# Jetson_Nano_without_CAN.net
KiCad netlist of a schematic drawn in EAGLE
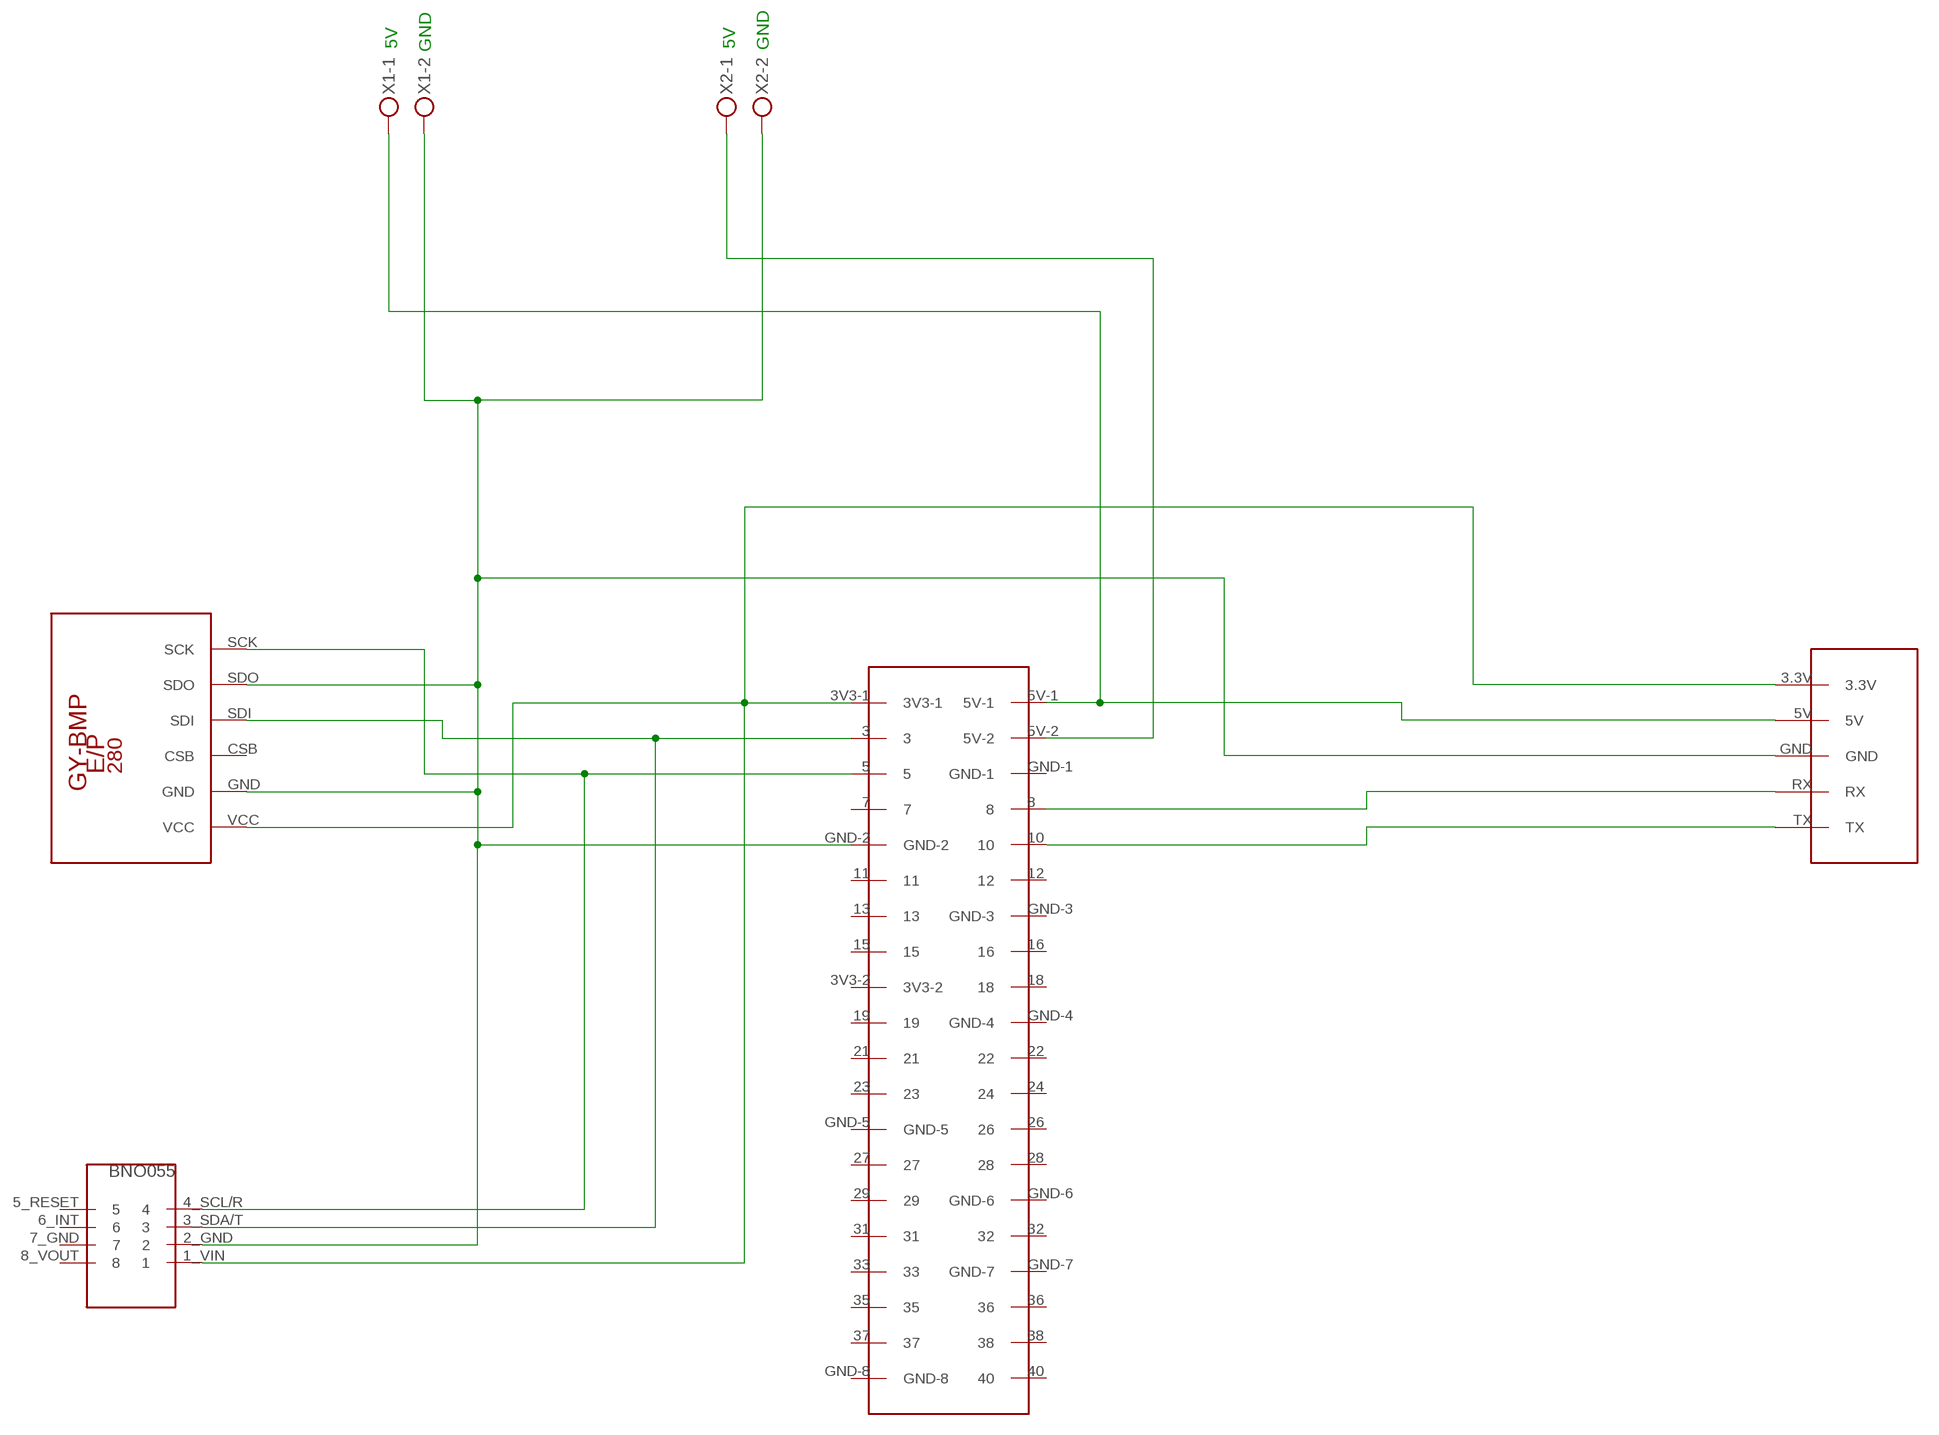
[diagram p0: schematic, sheet 1]

(export (version "E")
  (design (tool "Eeschema 10.0.6"))
  (components
    (comp (ref "JN1")
      (value "JETSON_NANO")
      (footprint "eagle-import:JETSON_NANO")
      (libsource (lib "eagle-import") (part "JETSON_NANO"))
    )
    (comp (ref "U$1")
      (value "GY-BPM280")
      (footprint "eagle-import:GY-BMP280-FOOTPRINT")
      (libsource (lib "eagle-import") (part "GY-BPM280"))
    )
    (comp (ref "U$2")
      (value "BNO055")
      (footprint "eagle-import:BNO055")
      (libsource (lib "eagle-import") (part "BNO055"))
    )
    (comp (ref "U$3")
      (value "WIRELESS_PINS")
      (footprint "eagle-import:WIRELESS_PINS")
      (libsource (lib "eagle-import") (part "WIRELESS_PINS"))
    )
    (comp (ref "X1")
      (value "MKDSN1,5/4-5,08")
      (footprint "eagle-import:MKDSN1,5_4-5,08")
      (libsource (lib "eagle-import") (part "MKDSN1,5/4-5,08"))
    )
    (comp (ref "X2")
      (value "MKDSN1,5/4-5,08")
      (footprint "eagle-import:MKDSN1,5_4-5,08")
      (libsource (lib "eagle-import") (part "MKDSN1,5/4-5,08"))
    )
  )
  (nets
    (net (code "1") (name "Net-(JN1-Pad8)") (class "Default")
      (node (ref "JN1") (pin "8") (pinfunction "8_8") (pintype "bidirectional"))
      (node (ref "U$3") (pin "RX") (pinfunction "RX_RX") (pintype "bidirectional"))
    )
    (net (code "2") (name "Net-(JN1-Pad10)") (class "Default")
      (node (ref "JN1") (pin "10") (pinfunction "10_10") (pintype "bidirectional"))
      (node (ref "U$3") (pin "TX") (pinfunction "TX_TX") (pintype "bidirectional"))
    )
    (net (code "3") (name "Net-(U$2-1)") (class "Default")
      (node (ref "JN1") (pin "3V3-1") (pinfunction "3V3-1_3V3-1") (pintype "bidirectional"))
      (node (ref "U$1") (pin "VCC") (pinfunction "VCC_VCC") (pintype "bidirectional"))
      (node (ref "U$2") (pin "1_VIN") (pinfunction "1_1_VIN") (pintype "bidirectional"))
      (node (ref "U$3") (pin "3.3V") (pinfunction "3.3V_3.3V") (pintype "bidirectional"))
    )
    (net (code "4") (name "Net-(U$2-2)") (class "Default")
      (node (ref "JN1") (pin "GND-2") (pinfunction "GND-2_GND-2") (pintype "bidirectional"))
      (node (ref "U$1") (pin "GND") (pinfunction "GND_GND") (pintype "bidirectional"))
      (node (ref "U$1") (pin "SDO") (pinfunction "SDO_SDO") (pintype "bidirectional"))
      (node (ref "U$2") (pin "2_GND") (pinfunction "2_2_GND") (pintype "bidirectional"))
      (node (ref "U$3") (pin "GND") (pinfunction "GND_GND") (pintype "bidirectional"))
      (node (ref "X1") (pin "2") (pinfunction "KL_2") (pintype "passive"))
      (node (ref "X2") (pin "2") (pinfunction "KL_2") (pintype "passive"))
    )
    (net (code "5") (name "Net-(U$2-3)") (class "Default")
      (node (ref "JN1") (pin "3") (pinfunction "3_3") (pintype "bidirectional"))
      (node (ref "U$1") (pin "SDI") (pinfunction "SDI_SDI") (pintype "bidirectional"))
      (node (ref "U$2") (pin "3_SDA/T") (pinfunction "3_3_SDA/T") (pintype "bidirectional"))
    )
    (net (code "6") (name "Net-(U$2-4)") (class "Default")
      (node (ref "JN1") (pin "5") (pinfunction "5_5") (pintype "bidirectional"))
      (node (ref "U$1") (pin "SCK") (pinfunction "SCK_SCK") (pintype "bidirectional"))
      (node (ref "U$2") (pin "4_SCL/R") (pinfunction "4_4_SCL/R") (pintype "bidirectional"))
    )
    (net (code "7") (name "Net-(X1A-KL)") (class "Default")
      (node (ref "JN1") (pin "5V-1") (pinfunction "5V-1_5V-1") (pintype "bidirectional"))
      (node (ref "U$3") (pin "5V") (pinfunction "5V_5V") (pintype "bidirectional"))
      (node (ref "X1") (pin "1") (pinfunction "KL_1") (pintype "passive"))
    )
    (net (code "8") (name "Net-(X2A-KL)") (class "Default")
      (node (ref "JN1") (pin "5V-2") (pinfunction "5V-2_5V-2") (pintype "bidirectional"))
      (node (ref "X2") (pin "1") (pinfunction "KL_1") (pintype "passive"))
    )
    (net (code "9") (name "unconnected-(JN1-Pad3V3-2)") (class "Default")
      (node (ref "JN1") (pin "3V3-2") (pinfunction "3V3-2_3V3-2") (pintype "bidirectional"))
    )
    (net (code "10") (name "unconnected-(JN1-Pad7)") (class "Default")
      (node (ref "JN1") (pin "7") (pinfunction "7_7") (pintype "bidirectional"))
    )
    (net (code "11") (name "unconnected-(JN1-Pad11)") (class "Default")
      (node (ref "JN1") (pin "11") (pinfunction "11_11") (pintype "bidirectional"))
    )
    (net (code "12") (name "unconnected-(JN1-Pad12)") (class "Default")
      (node (ref "JN1") (pin "12") (pinfunction "12_12") (pintype "bidirectional"))
    )
    (net (code "13") (name "unconnected-(JN1-Pad13)") (class "Default")
      (node (ref "JN1") (pin "13") (pinfunction "13_13") (pintype "bidirectional"))
    )
    (net (code "14") (name "unconnected-(JN1-Pad15)") (class "Default")
      (node (ref "JN1") (pin "15") (pinfunction "15_15") (pintype "bidirectional"))
    )
    (net (code "15") (name "unconnected-(JN1-Pad16)") (class "Default")
      (node (ref "JN1") (pin "16") (pinfunction "16_16") (pintype "bidirectional"))
    )
    (net (code "16") (name "unconnected-(JN1-Pad18)") (class "Default")
      (node (ref "JN1") (pin "18") (pinfunction "18_18") (pintype "bidirectional"))
    )
    (net (code "17") (name "unconnected-(JN1-Pad19)") (class "Default")
      (node (ref "JN1") (pin "19") (pinfunction "19_19") (pintype "bidirectional"))
    )
    (net (code "18") (name "unconnected-(JN1-Pad21)") (class "Default")
      (node (ref "JN1") (pin "21") (pinfunction "21_21") (pintype "bidirectional"))
    )
    (net (code "19") (name "unconnected-(JN1-Pad22)") (class "Default")
      (node (ref "JN1") (pin "22") (pinfunction "22_22") (pintype "bidirectional"))
    )
    (net (code "20") (name "unconnected-(JN1-Pad23)") (class "Default")
      (node (ref "JN1") (pin "23") (pinfunction "23_23") (pintype "bidirectional"))
    )
    (net (code "21") (name "unconnected-(JN1-Pad24)") (class "Default")
      (node (ref "JN1") (pin "24") (pinfunction "24_24") (pintype "bidirectional"))
    )
    (net (code "22") (name "unconnected-(JN1-Pad26)") (class "Default")
      (node (ref "JN1") (pin "26") (pinfunction "26_26") (pintype "bidirectional"))
    )
    (net (code "23") (name "unconnected-(JN1-Pad27)") (class "Default")
      (node (ref "JN1") (pin "27") (pinfunction "27_27") (pintype "bidirectional"))
    )
    (net (code "24") (name "unconnected-(JN1-Pad28)") (class "Default")
      (node (ref "JN1") (pin "28") (pinfunction "28_28") (pintype "bidirectional"))
    )
    (net (code "25") (name "unconnected-(JN1-Pad29)") (class "Default")
      (node (ref "JN1") (pin "29") (pinfunction "29_29") (pintype "bidirectional"))
    )
    (net (code "26") (name "unconnected-(JN1-Pad31)") (class "Default")
      (node (ref "JN1") (pin "31") (pinfunction "31_31") (pintype "bidirectional"))
    )
    (net (code "27") (name "unconnected-(JN1-Pad32)") (class "Default")
      (node (ref "JN1") (pin "32") (pinfunction "32_32") (pintype "bidirectional"))
    )
    (net (code "28") (name "unconnected-(JN1-Pad33)") (class "Default")
      (node (ref "JN1") (pin "33") (pinfunction "33_33") (pintype "bidirectional"))
    )
    (net (code "29") (name "unconnected-(JN1-Pad35)") (class "Default")
      (node (ref "JN1") (pin "35") (pinfunction "35_35") (pintype "bidirectional"))
    )
    (net (code "30") (name "unconnected-(JN1-Pad36)") (class "Default")
      (node (ref "JN1") (pin "36") (pinfunction "36_36") (pintype "bidirectional"))
    )
    (net (code "31") (name "unconnected-(JN1-Pad37)") (class "Default")
      (node (ref "JN1") (pin "37") (pinfunction "37_37") (pintype "bidirectional"))
    )
    (net (code "32") (name "unconnected-(JN1-Pad38)") (class "Default")
      (node (ref "JN1") (pin "38") (pinfunction "38_38") (pintype "bidirectional"))
    )
    (net (code "33") (name "unconnected-(JN1-Pad40)") (class "Default")
      (node (ref "JN1") (pin "40") (pinfunction "40_40") (pintype "bidirectional"))
    )
    (net (code "34") (name "unconnected-(JN1-PadGND-1)") (class "Default")
      (node (ref "JN1") (pin "GND-1") (pinfunction "GND-1_GND-1") (pintype "bidirectional"))
    )
    (net (code "35") (name "unconnected-(JN1-PadGND-3)") (class "Default")
      (node (ref "JN1") (pin "GND-3") (pinfunction "GND-3_GND-3") (pintype "bidirectional"))
    )
    (net (code "36") (name "unconnected-(JN1-PadGND-4)") (class "Default")
      (node (ref "JN1") (pin "GND-4") (pinfunction "GND-4_GND-4") (pintype "bidirectional"))
    )
    (net (code "37") (name "unconnected-(JN1-PadGND-5)") (class "Default")
      (node (ref "JN1") (pin "GND-5") (pinfunction "GND-5_GND-5") (pintype "bidirectional"))
    )
    (net (code "38") (name "unconnected-(JN1-PadGND-6)") (class "Default")
      (node (ref "JN1") (pin "GND-6") (pinfunction "GND-6_GND-6") (pintype "bidirectional"))
    )
    (net (code "39") (name "unconnected-(JN1-PadGND-7)") (class "Default")
      (node (ref "JN1") (pin "GND-7") (pinfunction "GND-7_GND-7") (pintype "bidirectional"))
    )
    (net (code "40") (name "unconnected-(JN1-PadGND-8)") (class "Default")
      (node (ref "JN1") (pin "GND-8") (pinfunction "GND-8_GND-8") (pintype "bidirectional"))
    )
    (net (code "41") (name "unconnected-(U$1-PadCSB)") (class "Default")
      (node (ref "U$1") (pin "CSB") (pinfunction "CSB_CSB") (pintype "bidirectional"))
    )
    (net (code "42") (name "unconnected-(U$2-5-Pad5_RESET)") (class "Default")
      (node (ref "U$2") (pin "5_RESET") (pinfunction "5_5_RESET") (pintype "bidirectional"))
    )
    (net (code "43") (name "unconnected-(U$2-6-Pad6_INT)") (class "Default")
      (node (ref "U$2") (pin "6_INT") (pinfunction "6_6_INT") (pintype "bidirectional"))
    )
    (net (code "44") (name "unconnected-(U$2-7-Pad7_GND)") (class "Default")
      (node (ref "U$2") (pin "7_GND") (pinfunction "7_7_GND") (pintype "bidirectional"))
    )
    (net (code "45") (name "unconnected-(U$2-8-Pad8_VOUT)") (class "Default")
      (node (ref "U$2") (pin "8_VOUT") (pinfunction "8_8_VOUT") (pintype "bidirectional"))
    )
  )
)
